# BEP31_Test_Interface4.net
KiCad netlist of a schematic drawn in EAGLE
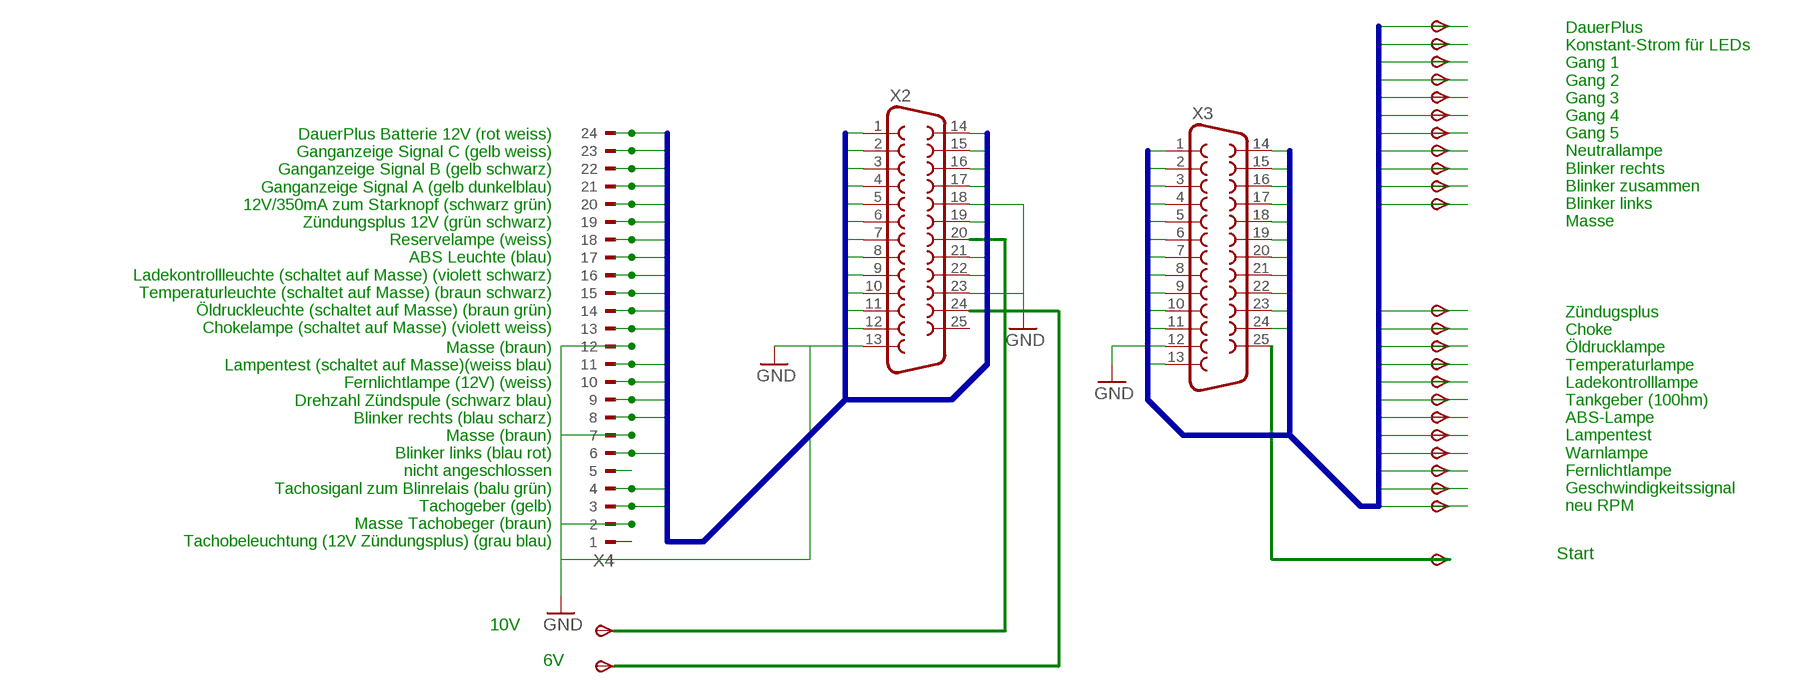
[diagram p0: schematic, sheet 1]
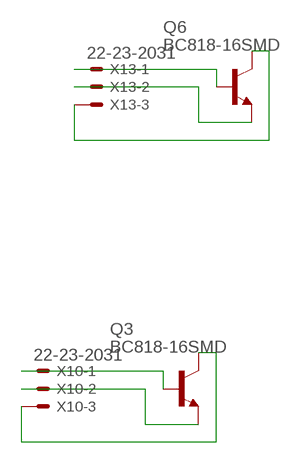
[diagram p1: schematic, sheet 2]
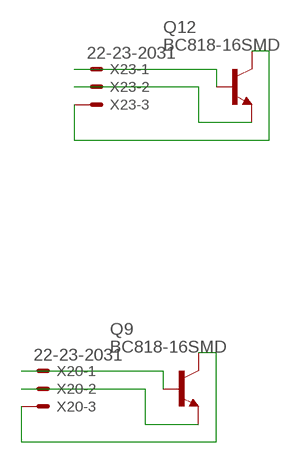
[diagram p2: schematic, sheet 3]
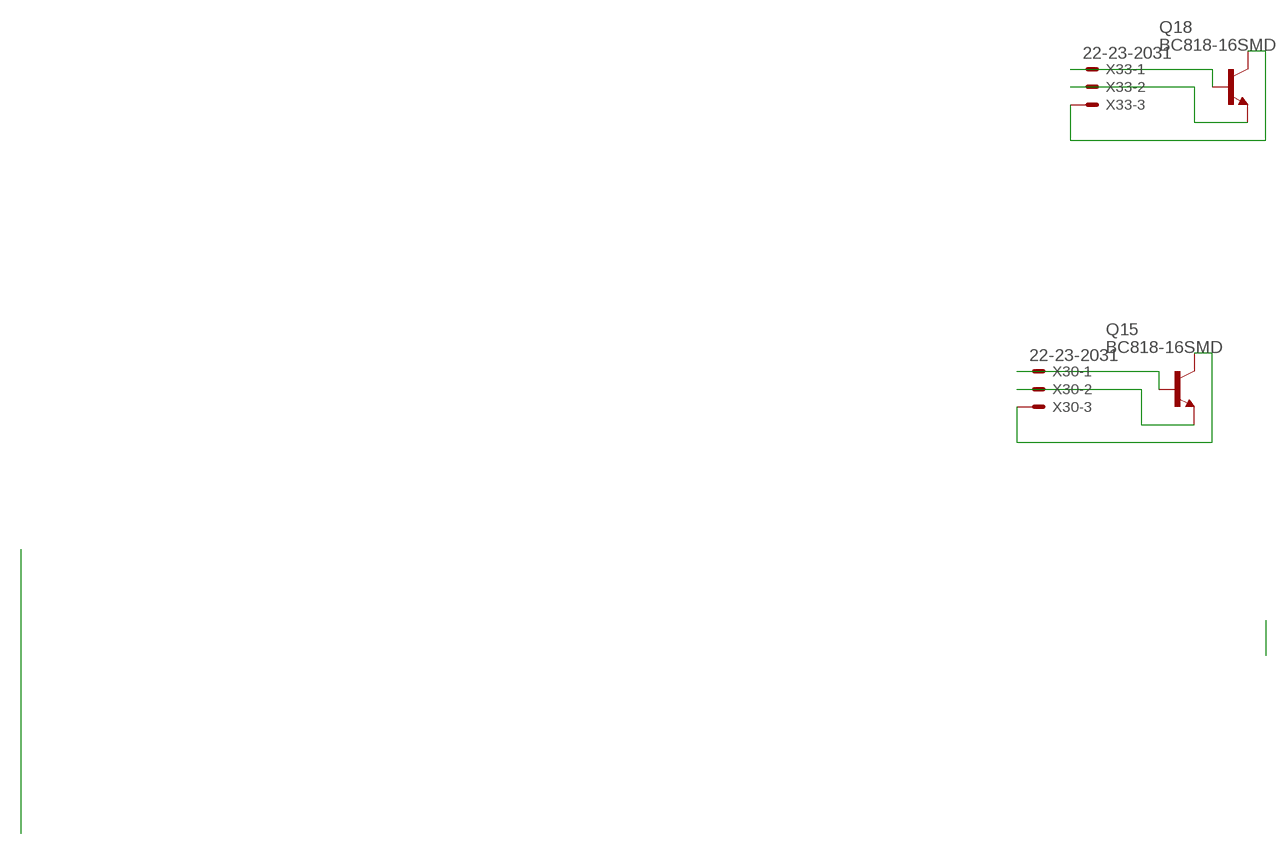
[diagram p3: schematic, sheet 4]
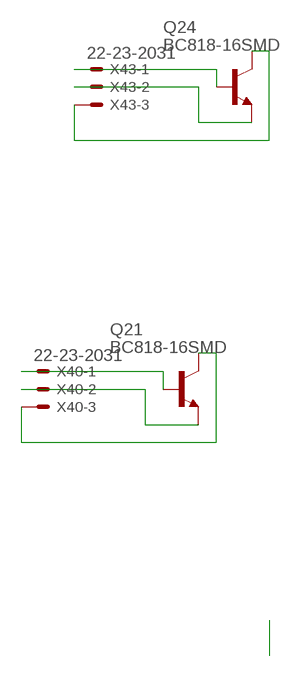
[diagram p4: schematic, sheet 5]

(export (version "E")
  (design (tool "Eeschema 10.0.6"))
  (components
    (comp (ref "TP1")
      (value "TPSFEDERPIN")
      (footprint "eagle-import:1,36ID")
      (libsource (lib "eagle-import") (part "TPSFEDERPIN"))
    )
    (comp (ref "TP2")
      (value "TPSFEDERPIN")
      (footprint "eagle-import:1,36ID")
      (libsource (lib "eagle-import") (part "TPSFEDERPIN"))
    )
    (comp (ref "TP3")
      (value "TPSFEDERPIN")
      (footprint "eagle-import:1,36ID")
      (libsource (lib "eagle-import") (part "TPSFEDERPIN"))
    )
    (comp (ref "TP4")
      (value "TPSFEDERPIN")
      (footprint "eagle-import:1,36ID")
      (libsource (lib "eagle-import") (part "TPSFEDERPIN"))
    )
    (comp (ref "TP5")
      (value "TPSFEDERPIN")
      (footprint "eagle-import:1,36ID")
      (libsource (lib "eagle-import") (part "TPSFEDERPIN"))
    )
    (comp (ref "TP6")
      (value "TPSFEDERPIN")
      (footprint "eagle-import:1,36ID")
      (libsource (lib "eagle-import") (part "TPSFEDERPIN"))
    )
    (comp (ref "TP7")
      (value "TPSFEDERPIN")
      (footprint "eagle-import:1,36ID")
      (libsource (lib "eagle-import") (part "TPSFEDERPIN"))
    )
    (comp (ref "TP8")
      (value "TPSFEDERPIN")
      (footprint "eagle-import:1,36ID")
      (libsource (lib "eagle-import") (part "TPSFEDERPIN"))
    )
    (comp (ref "TP9")
      (value "TPSFEDERPIN")
      (footprint "eagle-import:1,36ID")
      (libsource (lib "eagle-import") (part "TPSFEDERPIN"))
    )
    (comp (ref "TP10")
      (value "TPSFEDERPIN")
      (footprint "eagle-import:1,36ID")
      (libsource (lib "eagle-import") (part "TPSFEDERPIN"))
    )
    (comp (ref "TP11")
      (value "TPSFEDERPIN")
      (footprint "eagle-import:1,36ID")
      (libsource (lib "eagle-import") (part "TPSFEDERPIN"))
    )
    (comp (ref "TP12")
      (value "TPSFEDERPIN")
      (footprint "eagle-import:1,36ID")
      (libsource (lib "eagle-import") (part "TPSFEDERPIN"))
    )
    (comp (ref "TP13")
      (value "TPSFEDERPIN")
      (footprint "eagle-import:1,36ID")
      (libsource (lib "eagle-import") (part "TPSFEDERPIN"))
    )
    (comp (ref "TP14")
      (value "TPSFEDERPIN")
      (footprint "eagle-import:1,36ID")
      (libsource (lib "eagle-import") (part "TPSFEDERPIN"))
    )
    (comp (ref "TP15_10V")
      (value "TPSFEDERPIN")
      (footprint "eagle-import:1,36ID")
      (libsource (lib "eagle-import") (part "TPSFEDERPIN"))
    )
    (comp (ref "TP16")
      (value "TPSFEDERPIN")
      (footprint "eagle-import:1,36ID")
      (libsource (lib "eagle-import") (part "TPSFEDERPIN"))
    )
    (comp (ref "TP17")
      (value "TPSFEDERPIN")
      (footprint "eagle-import:1,36ID")
      (libsource (lib "eagle-import") (part "TPSFEDERPIN"))
    )
    (comp (ref "TP18")
      (value "TPSFEDERPIN")
      (footprint "eagle-import:1,36ID")
      (libsource (lib "eagle-import") (part "TPSFEDERPIN"))
    )
    (comp (ref "TP19")
      (value "TPSFEDERPIN")
      (footprint "eagle-import:1,36ID")
      (libsource (lib "eagle-import") (part "TPSFEDERPIN"))
    )
    (comp (ref "TP20_6V")
      (value "TPSFEDERPIN")
      (footprint "eagle-import:1,36ID")
      (libsource (lib "eagle-import") (part "TPSFEDERPIN"))
    )
    (comp (ref "TP21")
      (value "TPSFEDERPIN")
      (footprint "eagle-import:1,36ID")
      (libsource (lib "eagle-import") (part "TPSFEDERPIN"))
    )
    (comp (ref "TP22")
      (value "TPSFEDERPIN")
      (footprint "eagle-import:1,36ID")
      (libsource (lib "eagle-import") (part "TPSFEDERPIN"))
    )
    (comp (ref "TP23")
      (value "TPSFEDERPIN")
      (footprint "eagle-import:1,36ID")
      (libsource (lib "eagle-import") (part "TPSFEDERPIN"))
    )
    (comp (ref "TP24")
      (value "TPSFEDERPIN")
      (footprint "eagle-import:1,36ID")
      (libsource (lib "eagle-import") (part "TPSFEDERPIN"))
    )
    (comp (ref "TP25")
      (value "TPSFEDERPIN")
      (footprint "eagle-import:1,36ID")
      (libsource (lib "eagle-import") (part "TPSFEDERPIN"))
    )
    (comp (ref "TP26")
      (value "TPSFEDERPIN")
      (footprint "eagle-import:1,36ID")
      (libsource (lib "eagle-import") (part "TPSFEDERPIN"))
    )
    (comp (ref "X2")
      (value "F25H")
      (footprint "eagle-import:F25H")
      (libsource (lib "eagle-import") (part "F25H"))
    )
    (comp (ref "X3")
      (value "F25H")
      (footprint "eagle-import:F25H")
      (libsource (lib "eagle-import") (part "F25H"))
    )
    (comp (ref "X4")
      (value "CON_BMWTESTPINS")
      (footprint "eagle-import:24-TESTPIN_1,36ID")
      (libsource (lib "eagle-import") (part "CON_BMWTESTPINS"))
    )
    (comp (ref "Q3")
      (value "BC818-16SMD")
      (footprint "eagle-import:SOT23-BEC")
      (libsource (lib "eagle-import") (part "BC818SMD-16"))
    )
    (comp (ref "Q6")
      (value "BC818-16SMD")
      (footprint "eagle-import:SOT23-BEC")
      (libsource (lib "eagle-import") (part "BC818SMD-16"))
    )
    (comp (ref "X10")
      (value "22-23-2031")
      (footprint "eagle-import:22-23-2031")
      (fields (field (name "MF") "MOLEX"))
      (libsource (lib "eagle-import") (part "22-23-2031"))
    )
    (comp (ref "X13")
      (value "22-23-2031")
      (footprint "eagle-import:22-23-2031")
      (fields (field (name "MF") "MOLEX"))
      (libsource (lib "eagle-import") (part "22-23-2031"))
    )
    (comp (ref "Q15")
      (value "BC818-16SMD")
      (footprint "eagle-import:SOT23-BEC")
      (libsource (lib "eagle-import") (part "BC818SMD-16"))
    )
    (comp (ref "Q18")
      (value "BC818-16SMD")
      (footprint "eagle-import:SOT23-BEC")
      (libsource (lib "eagle-import") (part "BC818SMD-16"))
    )
    (comp (ref "X30")
      (value "22-23-2031")
      (footprint "eagle-import:22-23-2031")
      (fields (field (name "MF") "MOLEX"))
      (libsource (lib "eagle-import") (part "22-23-2031"))
    )
    (comp (ref "X33")
      (value "22-23-2031")
      (footprint "eagle-import:22-23-2031")
      (fields (field (name "MF") "MOLEX"))
      (libsource (lib "eagle-import") (part "22-23-2031"))
    )
    (comp (ref "Q21")
      (value "BC818-16SMD")
      (footprint "eagle-import:SOT23-BEC")
      (libsource (lib "eagle-import") (part "BC818SMD-16"))
    )
    (comp (ref "Q24")
      (value "BC818-16SMD")
      (footprint "eagle-import:SOT23-BEC")
      (libsource (lib "eagle-import") (part "BC818SMD-16"))
    )
    (comp (ref "X40")
      (value "22-23-2031")
      (footprint "eagle-import:22-23-2031")
      (fields (field (name "MF") "MOLEX"))
      (libsource (lib "eagle-import") (part "22-23-2031"))
    )
    (comp (ref "X43")
      (value "22-23-2031")
      (footprint "eagle-import:22-23-2031")
      (fields (field (name "MF") "MOLEX"))
      (libsource (lib "eagle-import") (part "22-23-2031"))
    )
    (comp (ref "Q9")
      (value "BC818-16SMD")
      (footprint "eagle-import:SOT23-BEC")
      (libsource (lib "eagle-import") (part "BC818SMD-16"))
    )
    (comp (ref "Q12")
      (value "BC818-16SMD")
      (footprint "eagle-import:SOT23-BEC")
      (libsource (lib "eagle-import") (part "BC818SMD-16"))
    )
    (comp (ref "X20")
      (value "22-23-2031")
      (footprint "eagle-import:22-23-2031")
      (fields (field (name "MF") "MOLEX"))
      (libsource (lib "eagle-import") (part "22-23-2031"))
    )
    (comp (ref "X23")
      (value "22-23-2031")
      (footprint "eagle-import:22-23-2031")
      (fields (field (name "MF") "MOLEX"))
      (libsource (lib "eagle-import") (part "22-23-2031"))
    )
  )
  (nets
    (net (code "1") (name "BMW1") (class "Default")
      (node (ref "X2") (pin "1") (pinfunction "1_1") (pintype "passive"))
      (node (ref "X4") (pin "P24") (pinfunction "24_P24") (pintype "passive"))
    )
    (net (code "2") (name "BMW2") (class "Default")
      (node (ref "X2") (pin "2") (pinfunction "2_2") (pintype "passive"))
      (node (ref "X4") (pin "P23") (pinfunction "23_P23") (pintype "passive"))
    )
    (net (code "3") (name "BMW3") (class "Default")
      (node (ref "X2") (pin "3") (pinfunction "3_3") (pintype "passive"))
      (node (ref "X4") (pin "P22") (pinfunction "22_P22") (pintype "passive"))
    )
    (net (code "4") (name "BMW4") (class "Default")
      (node (ref "X2") (pin "4") (pinfunction "4_4") (pintype "passive"))
      (node (ref "X4") (pin "P21") (pinfunction "21_P21") (pintype "passive"))
    )
    (net (code "5") (name "BMW5") (class "Default")
      (node (ref "X2") (pin "5") (pinfunction "5_5") (pintype "passive"))
      (node (ref "X4") (pin "P20") (pinfunction "20_P20") (pintype "passive"))
    )
    (net (code "6") (name "BMW6") (class "Default")
      (node (ref "X2") (pin "6") (pinfunction "6_6") (pintype "passive"))
      (node (ref "X4") (pin "P19") (pinfunction "19_P19") (pintype "passive"))
    )
    (net (code "7") (name "BMW7") (class "Default")
      (node (ref "X2") (pin "7") (pinfunction "7_7") (pintype "passive"))
      (node (ref "X4") (pin "P18") (pinfunction "18_P18") (pintype "passive"))
    )
    (net (code "8") (name "BMW8") (class "Default")
      (node (ref "X2") (pin "8") (pinfunction "8_8") (pintype "passive"))
      (node (ref "X4") (pin "P17") (pinfunction "17_P17") (pintype "passive"))
    )
    (net (code "9") (name "BMW9") (class "Default")
      (node (ref "X2") (pin "9") (pinfunction "9_9") (pintype "passive"))
      (node (ref "X4") (pin "P16") (pinfunction "16_P16") (pintype "passive"))
    )
    (net (code "10") (name "BMW10") (class "Default")
      (node (ref "X2") (pin "10") (pinfunction "10_10") (pintype "passive"))
      (node (ref "X4") (pin "P15") (pinfunction "15_P15") (pintype "passive"))
    )
    (net (code "11") (name "BMW11") (class "Default")
      (node (ref "X2") (pin "11") (pinfunction "11_11") (pintype "passive"))
      (node (ref "X4") (pin "P14") (pinfunction "14_P14") (pintype "passive"))
    )
    (net (code "12") (name "BMW12") (class "Default")
      (node (ref "X2") (pin "12") (pinfunction "12_12") (pintype "passive"))
      (node (ref "X4") (pin "P13") (pinfunction "13_P13") (pintype "passive"))
    )
    (net (code "13") (name "BMW14") (class "Default")
      (node (ref "X2") (pin "14") (pinfunction "14_14") (pintype "passive"))
      (node (ref "X4") (pin "P11") (pinfunction "11_P11") (pintype "passive"))
    )
    (net (code "14") (name "BMW15") (class "Default")
      (node (ref "X2") (pin "15") (pinfunction "15_15") (pintype "passive"))
      (node (ref "X4") (pin "P10") (pinfunction "10_P10") (pintype "passive"))
    )
    (net (code "15") (name "BMW16") (class "Default")
      (node (ref "X2") (pin "16") (pinfunction "16_16") (pintype "passive"))
      (node (ref "X4") (pin "P9") (pinfunction "9_P9") (pintype "passive"))
    )
    (net (code "16") (name "BMW17") (class "Default")
      (node (ref "X2") (pin "17") (pinfunction "17_17") (pintype "passive"))
      (node (ref "X4") (pin "P8") (pinfunction "8_P8") (pintype "passive"))
    )
    (net (code "17") (name "BMW19") (class "Default")
      (node (ref "X2") (pin "19") (pinfunction "19_19") (pintype "passive"))
      (node (ref "X4") (pin "P6") (pinfunction "6_P6") (pintype "passive"))
    )
    (net (code "18") (name "BMW21") (class "Default")
      (node (ref "X2") (pin "21") (pinfunction "21_21") (pintype "passive"))
      (node (ref "X4") (pin "P4") (pinfunction "4_P4") (pintype "passive"))
    )
    (net (code "19") (name "BMW22") (class "Default")
      (node (ref "X2") (pin "22") (pinfunction "22_22") (pintype "passive"))
      (node (ref "X4") (pin "P3") (pinfunction "3_P3") (pintype "passive"))
    )
    (net (code "20") (name "GND") (class "Default")
      (node (ref "X2") (pin "13") (pinfunction "13_13") (pintype "passive"))
      (node (ref "X2") (pin "18") (pinfunction "18_18") (pintype "passive"))
      (node (ref "X2") (pin "23") (pinfunction "23_23") (pintype "passive"))
      (node (ref "X3") (pin "12") (pinfunction "12_12") (pintype "passive"))
      (node (ref "X4") (pin "P12") (pinfunction "12_P12") (pintype "passive"))
      (node (ref "X4") (pin "P2") (pinfunction "2_P2") (pintype "passive"))
      (node (ref "X4") (pin "P7") (pinfunction "7_P7") (pintype "passive"))
    )
    (net (code "21") (name "Net-(TP14-PP)") (class "Default")
      (node (ref "TP14") (pin "P$1") (pinfunction "PP_P$1") (pintype "input"))
      (node (ref "X3") (pin "25") (pinfunction "25_25") (pintype "passive"))
    )
    (net (code "22") (name "Net-(TP15_10V-PP)") (class "Default")
      (node (ref "TP15_10V") (pin "P$1") (pinfunction "PP_P$1") (pintype "input"))
      (node (ref "X2") (pin "20") (pinfunction "20_20") (pintype "passive"))
    )
    (net (code "23") (name "Net-(TP20_6V-PP)") (class "Default")
      (node (ref "TP20_6V") (pin "P$1") (pinfunction "PP_P$1") (pintype "input"))
      (node (ref "X2") (pin "24") (pinfunction "24_24") (pintype "passive"))
    )
    (net (code "24") (name "Net-(X10A-S)") (class "Default")
      (node (ref "Q3") (pin "B") (pinfunction "B_B") (pintype "passive"))
      (node (ref "X10") (pin "1") (pinfunction "S_1") (pintype "passive"))
    )
    (net (code "25") (name "Net-(X10B-S)") (class "Default")
      (node (ref "Q3") (pin "E") (pinfunction "E_E") (pintype "passive"))
      (node (ref "X10") (pin "2") (pinfunction "S_2") (pintype "passive"))
    )
    (net (code "26") (name "Net-(X10C-S)") (class "Default")
      (node (ref "Q3") (pin "C") (pinfunction "C_C") (pintype "passive"))
      (node (ref "X10") (pin "3") (pinfunction "S_3") (pintype "passive"))
    )
    (net (code "27") (name "Net-(X13A-S)") (class "Default")
      (node (ref "Q6") (pin "B") (pinfunction "B_B") (pintype "passive"))
      (node (ref "X13") (pin "1") (pinfunction "S_1") (pintype "passive"))
    )
    (net (code "28") (name "Net-(X13B-S)") (class "Default")
      (node (ref "Q6") (pin "E") (pinfunction "E_E") (pintype "passive"))
      (node (ref "X13") (pin "2") (pinfunction "S_2") (pintype "passive"))
    )
    (net (code "29") (name "Net-(X13C-S)") (class "Default")
      (node (ref "Q6") (pin "C") (pinfunction "C_C") (pintype "passive"))
      (node (ref "X13") (pin "3") (pinfunction "S_3") (pintype "passive"))
    )
    (net (code "30") (name "Net-(X20A-S)") (class "Default")
      (node (ref "Q9") (pin "B") (pinfunction "B_B") (pintype "passive"))
      (node (ref "X20") (pin "1") (pinfunction "S_1") (pintype "passive"))
    )
    (net (code "31") (name "Net-(X20B-S)") (class "Default")
      (node (ref "Q9") (pin "E") (pinfunction "E_E") (pintype "passive"))
      (node (ref "X20") (pin "2") (pinfunction "S_2") (pintype "passive"))
    )
    (net (code "32") (name "Net-(X20C-S)") (class "Default")
      (node (ref "Q9") (pin "C") (pinfunction "C_C") (pintype "passive"))
      (node (ref "X20") (pin "3") (pinfunction "S_3") (pintype "passive"))
    )
    (net (code "33") (name "Net-(X23A-S)") (class "Default")
      (node (ref "Q12") (pin "B") (pinfunction "B_B") (pintype "passive"))
      (node (ref "X23") (pin "1") (pinfunction "S_1") (pintype "passive"))
    )
    (net (code "34") (name "Net-(X23B-S)") (class "Default")
      (node (ref "Q12") (pin "E") (pinfunction "E_E") (pintype "passive"))
      (node (ref "X23") (pin "2") (pinfunction "S_2") (pintype "passive"))
    )
    (net (code "35") (name "Net-(X23C-S)") (class "Default")
      (node (ref "Q12") (pin "C") (pinfunction "C_C") (pintype "passive"))
      (node (ref "X23") (pin "3") (pinfunction "S_3") (pintype "passive"))
    )
    (net (code "36") (name "Net-(X30A-S)") (class "Default")
      (node (ref "Q15") (pin "B") (pinfunction "B_B") (pintype "passive"))
      (node (ref "X30") (pin "1") (pinfunction "S_1") (pintype "passive"))
    )
    (net (code "37") (name "Net-(X30B-S)") (class "Default")
      (node (ref "Q15") (pin "E") (pinfunction "E_E") (pintype "passive"))
      (node (ref "X30") (pin "2") (pinfunction "S_2") (pintype "passive"))
    )
    (net (code "38") (name "Net-(X30C-S)") (class "Default")
      (node (ref "Q15") (pin "C") (pinfunction "C_C") (pintype "passive"))
      (node (ref "X30") (pin "3") (pinfunction "S_3") (pintype "passive"))
    )
    (net (code "39") (name "Net-(X33A-S)") (class "Default")
      (node (ref "Q18") (pin "B") (pinfunction "B_B") (pintype "passive"))
      (node (ref "X33") (pin "1") (pinfunction "S_1") (pintype "passive"))
    )
    (net (code "40") (name "Net-(X33B-S)") (class "Default")
      (node (ref "Q18") (pin "E") (pinfunction "E_E") (pintype "passive"))
      (node (ref "X33") (pin "2") (pinfunction "S_2") (pintype "passive"))
    )
    (net (code "41") (name "Net-(X33C-S)") (class "Default")
      (node (ref "Q18") (pin "C") (pinfunction "C_C") (pintype "passive"))
      (node (ref "X33") (pin "3") (pinfunction "S_3") (pintype "passive"))
    )
    (net (code "42") (name "Net-(X40A-S)") (class "Default")
      (node (ref "Q21") (pin "B") (pinfunction "B_B") (pintype "passive"))
      (node (ref "X40") (pin "1") (pinfunction "S_1") (pintype "passive"))
    )
    (net (code "43") (name "Net-(X40B-S)") (class "Default")
      (node (ref "Q21") (pin "E") (pinfunction "E_E") (pintype "passive"))
      (node (ref "X40") (pin "2") (pinfunction "S_2") (pintype "passive"))
    )
    (net (code "44") (name "Net-(X40C-S)") (class "Default")
      (node (ref "Q21") (pin "C") (pinfunction "C_C") (pintype "passive"))
      (node (ref "X40") (pin "3") (pinfunction "S_3") (pintype "passive"))
    )
    (net (code "45") (name "Net-(X43A-S)") (class "Default")
      (node (ref "Q24") (pin "B") (pinfunction "B_B") (pintype "passive"))
      (node (ref "X43") (pin "1") (pinfunction "S_1") (pintype "passive"))
    )
    (net (code "46") (name "Net-(X43B-S)") (class "Default")
      (node (ref "Q24") (pin "E") (pinfunction "E_E") (pintype "passive"))
      (node (ref "X43") (pin "2") (pinfunction "S_2") (pintype "passive"))
    )
    (net (code "47") (name "Net-(X43C-S)") (class "Default")
      (node (ref "Q24") (pin "C") (pinfunction "C_C") (pintype "passive"))
      (node (ref "X43") (pin "3") (pinfunction "S_3") (pintype "passive"))
    )
    (net (code "48") (name "WAGO1") (class "Default")
      (node (ref "TP1") (pin "P$1") (pinfunction "PP_P$1") (pintype "input"))
      (node (ref "X3") (pin "1") (pinfunction "1_1") (pintype "passive"))
    )
    (net (code "49") (name "WAGO2") (class "Default")
      (node (ref "TP2") (pin "P$1") (pinfunction "PP_P$1") (pintype "input"))
      (node (ref "X3") (pin "2") (pinfunction "2_2") (pintype "passive"))
    )
    (net (code "50") (name "WAGO3") (class "Default")
      (node (ref "TP3") (pin "P$1") (pinfunction "PP_P$1") (pintype "input"))
      (node (ref "X3") (pin "3") (pinfunction "3_3") (pintype "passive"))
    )
    (net (code "51") (name "WAGO4") (class "Default")
      (node (ref "TP4") (pin "P$1") (pinfunction "PP_P$1") (pintype "input"))
      (node (ref "X3") (pin "4") (pinfunction "4_4") (pintype "passive"))
    )
    (net (code "52") (name "WAGO5") (class "Default")
      (node (ref "TP5") (pin "P$1") (pinfunction "PP_P$1") (pintype "input"))
      (node (ref "X3") (pin "5") (pinfunction "5_5") (pintype "passive"))
    )
    (net (code "53") (name "WAGO6") (class "Default")
      (node (ref "TP6") (pin "P$1") (pinfunction "PP_P$1") (pintype "input"))
      (node (ref "X3") (pin "6") (pinfunction "6_6") (pintype "passive"))
    )
    (net (code "54") (name "WAGO7") (class "Default")
      (node (ref "TP7") (pin "P$1") (pinfunction "PP_P$1") (pintype "input"))
      (node (ref "X3") (pin "7") (pinfunction "7_7") (pintype "passive"))
    )
    (net (code "55") (name "WAGO8") (class "Default")
      (node (ref "TP8") (pin "P$1") (pinfunction "PP_P$1") (pintype "input"))
      (node (ref "X3") (pin "8") (pinfunction "8_8") (pintype "passive"))
    )
    (net (code "56") (name "WAGO9") (class "Default")
      (node (ref "TP9") (pin "P$1") (pinfunction "PP_P$1") (pintype "input"))
      (node (ref "X3") (pin "9") (pinfunction "9_9") (pintype "passive"))
    )
    (net (code "57") (name "WAGO10") (class "Default")
      (node (ref "TP10") (pin "P$1") (pinfunction "PP_P$1") (pintype "input"))
      (node (ref "X3") (pin "10") (pinfunction "10_10") (pintype "passive"))
    )
    (net (code "58") (name "WAGO11") (class "Default")
      (node (ref "TP11") (pin "P$1") (pinfunction "PP_P$1") (pintype "input"))
      (node (ref "X3") (pin "11") (pinfunction "11_11") (pintype "passive"))
    )
    (net (code "59") (name "WAGO13") (class "Default")
      (node (ref "TP12") (pin "P$1") (pinfunction "PP_P$1") (pintype "input"))
      (node (ref "X3") (pin "13") (pinfunction "13_13") (pintype "passive"))
    )
    (net (code "60") (name "WAGO14") (class "Default")
      (node (ref "TP16") (pin "P$1") (pinfunction "PP_P$1") (pintype "input"))
      (node (ref "X3") (pin "14") (pinfunction "14_14") (pintype "passive"))
    )
    (net (code "61") (name "WAGO15") (class "Default")
      (node (ref "TP17") (pin "P$1") (pinfunction "PP_P$1") (pintype "input"))
      (node (ref "X3") (pin "15") (pinfunction "15_15") (pintype "passive"))
    )
    (net (code "62") (name "WAGO16") (class "Default")
      (node (ref "TP18") (pin "P$1") (pinfunction "PP_P$1") (pintype "input"))
      (node (ref "X3") (pin "16") (pinfunction "16_16") (pintype "passive"))
    )
    (net (code "63") (name "WAGO17") (class "Default")
      (node (ref "TP19") (pin "P$1") (pinfunction "PP_P$1") (pintype "input"))
      (node (ref "X3") (pin "17") (pinfunction "17_17") (pintype "passive"))
    )
    (net (code "64") (name "WAGO18") (class "Default")
      (node (ref "TP21") (pin "P$1") (pinfunction "PP_P$1") (pintype "input"))
      (node (ref "X3") (pin "18") (pinfunction "18_18") (pintype "passive"))
    )
    (net (code "65") (name "WAGO19") (class "Default")
      (node (ref "TP22") (pin "P$1") (pinfunction "PP_P$1") (pintype "input"))
      (node (ref "X3") (pin "19") (pinfunction "19_19") (pintype "passive"))
    )
    (net (code "66") (name "WAGO20") (class "Default")
      (node (ref "TP23") (pin "P$1") (pinfunction "PP_P$1") (pintype "input"))
      (node (ref "X3") (pin "20") (pinfunction "20_20") (pintype "passive"))
    )
    (net (code "67") (name "WAGO21") (class "Default")
      (node (ref "TP24") (pin "P$1") (pinfunction "PP_P$1") (pintype "input"))
      (node (ref "X3") (pin "21") (pinfunction "21_21") (pintype "passive"))
    )
    (net (code "68") (name "WAGO22") (class "Default")
      (node (ref "TP25") (pin "P$1") (pinfunction "PP_P$1") (pintype "input"))
      (node (ref "X3") (pin "22") (pinfunction "22_22") (pintype "passive"))
    )
    (net (code "69") (name "WAGO23") (class "Default")
      (node (ref "TP26") (pin "P$1") (pinfunction "PP_P$1") (pintype "input"))
      (node (ref "X3") (pin "23") (pinfunction "23_23") (pintype "passive"))
    )
    (net (code "70") (name "WAGO24") (class "Default")
      (node (ref "TP13") (pin "P$1") (pinfunction "PP_P$1") (pintype "input"))
      (node (ref "X3") (pin "24") (pinfunction "24_24") (pintype "passive"))
    )
    (net (code "71") (name "unconnected-(X2-Pad25)") (class "Default")
      (node (ref "X2") (pin "25") (pinfunction "25_25") (pintype "passive"))
    )
    (net (code "72") (name "unconnected-(X4-1-PadP1)") (class "Default")
      (node (ref "X4") (pin "P1") (pinfunction "1_P1") (pintype "passive"))
    )
    (net (code "73") (name "unconnected-(X4-5-PadP5)") (class "Default")
      (node (ref "X4") (pin "P5") (pinfunction "5_P5") (pintype "passive"))
    )
  )
)
